# ECG.net
KiCad netlist of a schematic drawn in EAGLE
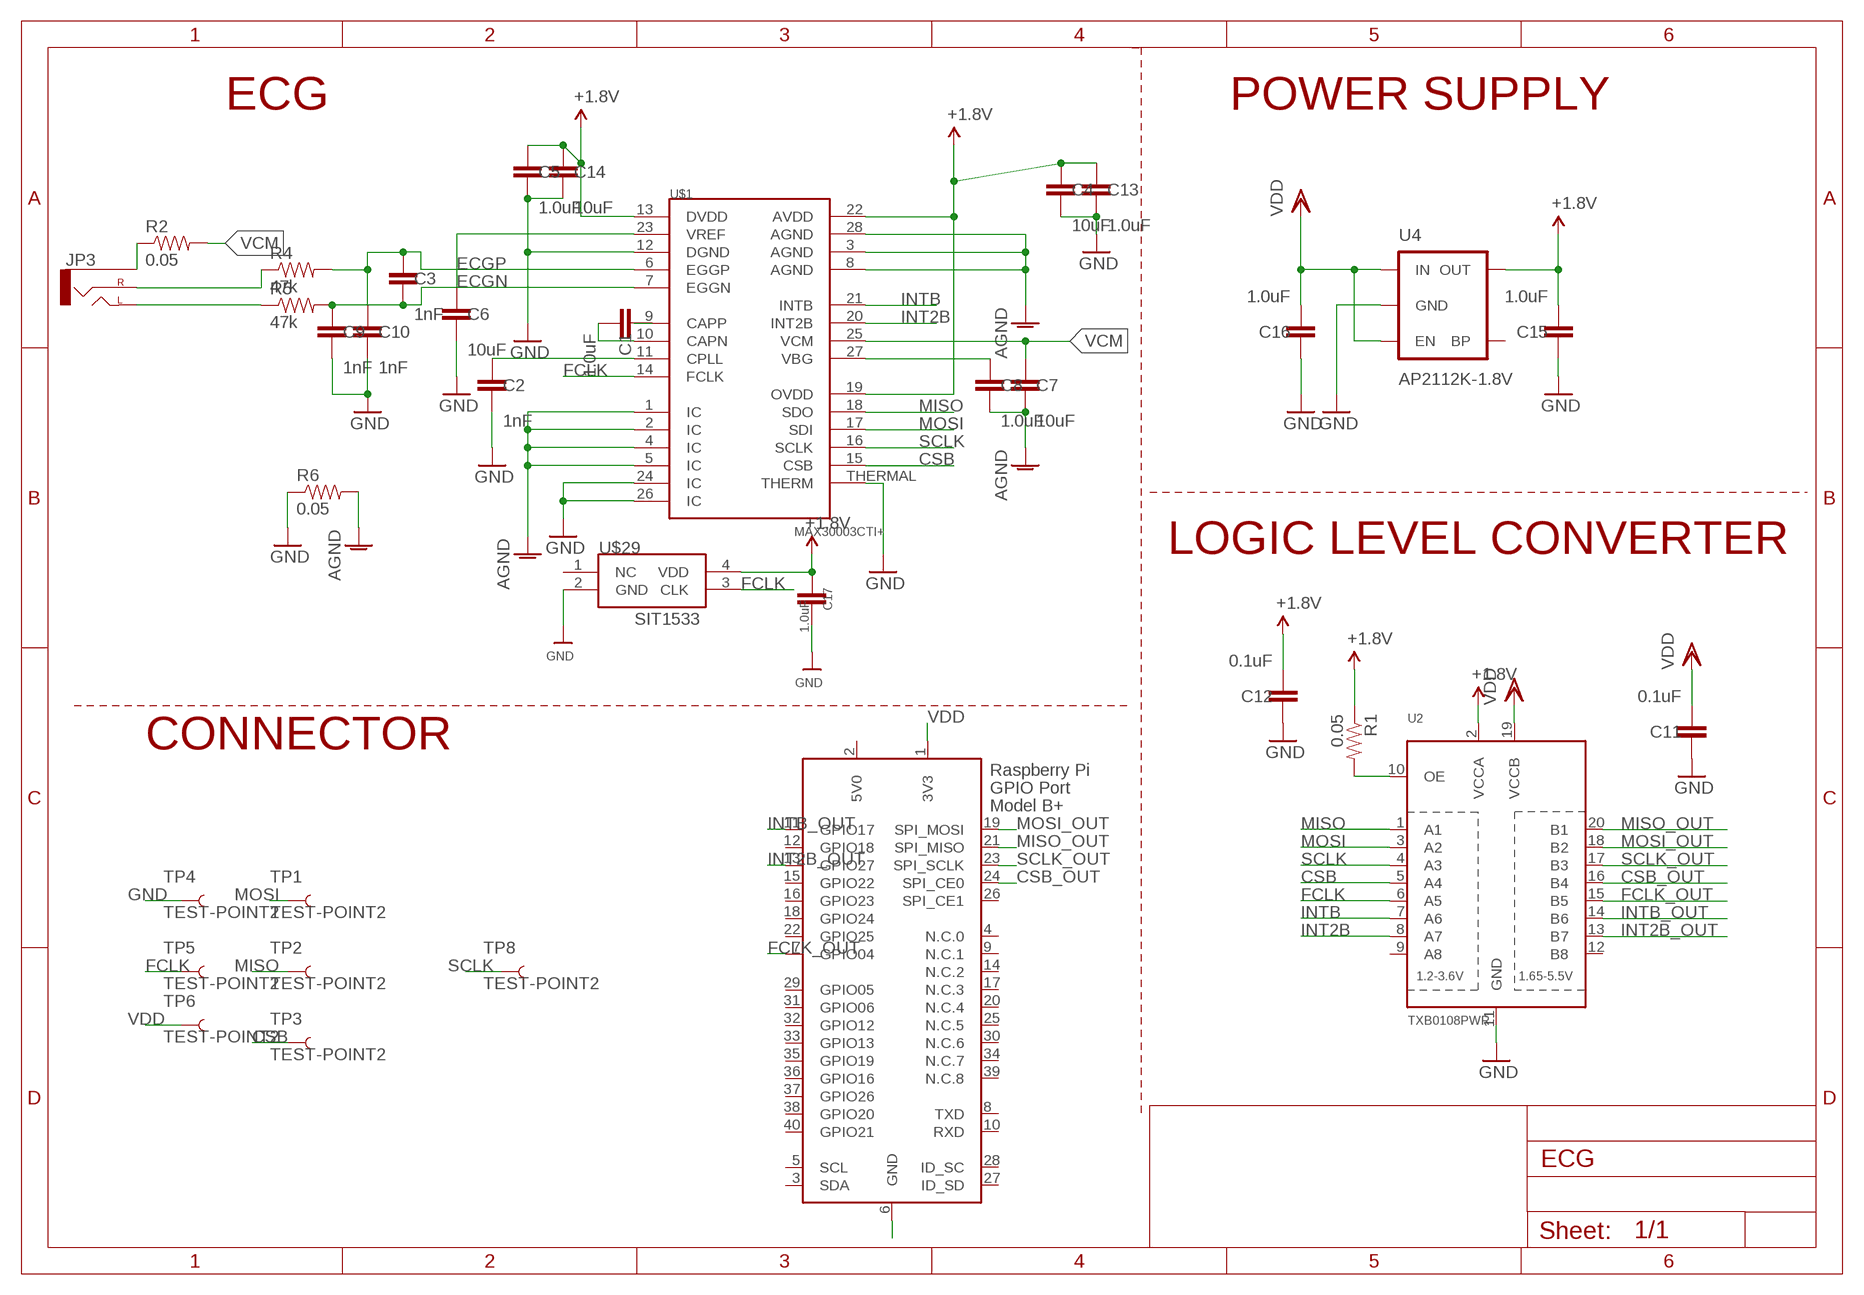
[diagram p0: schematic, sheet 1]

(export (version "E")
  (design (tool "Eeschema 10.0.6"))
  (components
    (comp (ref "C1")
      (value "1.0uF")
      (footprint "eagle-import:0603")
      (libsource (lib "eagle-import") (part "1.0UF-0603-16V-10%"))
    )
    (comp (ref "C2")
      (value "1nF")
      (footprint "eagle-import:0603")
      (libsource (lib "eagle-import") (part "1.0NF/1000PF-0603-50V-10%"))
    )
    (comp (ref "C3")
      (value "1nF")
      (footprint "eagle-import:0603")
      (libsource (lib "eagle-import") (part "1.0NF/1000PF-0603-50V-10%"))
    )
    (comp (ref "C4")
      (value "10uF")
      (footprint "eagle-import:0603")
      (libsource (lib "eagle-import") (part "10UF-0603-6.3V-20%"))
    )
    (comp (ref "C5")
      (value "1.0uF")
      (footprint "eagle-import:0603")
      (libsource (lib "eagle-import") (part "1.0UF-0603-16V-10%"))
    )
    (comp (ref "C6")
      (value "10uF")
      (footprint "eagle-import:0603")
      (libsource (lib "eagle-import") (part "10UF-0603-6.3V-20%"))
    )
    (comp (ref "C7")
      (value "10uF")
      (footprint "eagle-import:0603")
      (libsource (lib "eagle-import") (part "10UF-0603-6.3V-20%"))
    )
    (comp (ref "C8")
      (value "1.0uF")
      (footprint "eagle-import:0603")
      (libsource (lib "eagle-import") (part "1.0UF-0603-16V-10%"))
    )
    (comp (ref "C9")
      (value "1nF")
      (footprint "eagle-import:0603")
      (libsource (lib "eagle-import") (part "1.0NF/1000PF-0603-50V-10%"))
    )
    (comp (ref "C10")
      (value "1nF")
      (footprint "eagle-import:0603")
      (libsource (lib "eagle-import") (part "1.0NF/1000PF-0603-50V-10%"))
    )
    (comp (ref "C11")
      (value "0.1uF")
      (footprint "eagle-import:0603")
      (libsource (lib "eagle-import") (part "0.1UF-0603-25V-(+80/-20%)"))
    )
    (comp (ref "C12")
      (value "0.1uF")
      (footprint "eagle-import:0603")
      (libsource (lib "eagle-import") (part "0.1UF-0603-25V-(+80/-20%)"))
    )
    (comp (ref "C13")
      (value "1.0uF")
      (footprint "eagle-import:0603")
      (libsource (lib "eagle-import") (part "1.0UF-0603-16V-10%"))
    )
    (comp (ref "C14")
      (value "10uF")
      (footprint "eagle-import:0603")
      (libsource (lib "eagle-import") (part "10UF-0603-6.3V-20%"))
    )
    (comp (ref "C15")
      (value "1.0uF")
      (footprint "eagle-import:0603")
      (libsource (lib "eagle-import") (part "1.0UF-0603-16V-10%"))
    )
    (comp (ref "C16")
      (value "1.0uF")
      (footprint "eagle-import:0603")
      (libsource (lib "eagle-import") (part "1.0UF-0603-16V-10%"))
    )
    (comp (ref "C17")
      (value "1.0uF")
      (footprint "eagle-import:0603")
      (libsource (lib "eagle-import") (part "1.0UF-0603-16V-10%"))
    )
    (comp (ref "JP3")
      (value "AUDIO-JACKSMD2")
      (footprint "eagle-import:AUDIO-JACK-3.5MM-SMD")
      (libsource (lib "eagle-import") (part "AUDIO-JACKSMD2"))
    )
    (comp (ref "R1")
      (value "0.05")
      (footprint "eagle-import:0603")
      (libsource (lib "eagle-import") (part "0.05OHM-0603-1/5W-1%"))
    )
    (comp (ref "R2")
      (value "0.05")
      (footprint "eagle-import:0603")
      (libsource (lib "eagle-import") (part "0.05OHM-0603-1/5W-1%"))
    )
    (comp (ref "R4")
      (value "47k")
      (footprint "eagle-import:0603")
      (libsource (lib "eagle-import") (part "47KOHM-0603-1/10W-1%"))
    )
    (comp (ref "R5")
      (value "47k")
      (footprint "eagle-import:0603")
      (libsource (lib "eagle-import") (part "47KOHM-0603-1/10W-1%"))
    )
    (comp (ref "R6")
      (value "0.05")
      (footprint "eagle-import:0603")
      (libsource (lib "eagle-import") (part "0.05OHM-0603-1/5W-1%"))
    )
    (comp (ref "TP1")
      (value "TEST-POINT2")
      (footprint "eagle-import:PAD.02X.02")
      (libsource (lib "eagle-import") (part "TEST-POINT2"))
    )
    (comp (ref "TP2")
      (value "TEST-POINT2")
      (footprint "eagle-import:PAD.02X.02")
      (libsource (lib "eagle-import") (part "TEST-POINT2"))
    )
    (comp (ref "TP3")
      (value "TEST-POINT2")
      (footprint "eagle-import:PAD.02X.02")
      (libsource (lib "eagle-import") (part "TEST-POINT2"))
    )
    (comp (ref "TP4")
      (value "TEST-POINT2")
      (footprint "eagle-import:PAD.02X.02")
      (libsource (lib "eagle-import") (part "TEST-POINT2"))
    )
    (comp (ref "TP5")
      (value "TEST-POINT2")
      (footprint "eagle-import:PAD.02X.02")
      (libsource (lib "eagle-import") (part "TEST-POINT2"))
    )
    (comp (ref "TP6")
      (value "TEST-POINT2")
      (footprint "eagle-import:PAD.02X.02")
      (libsource (lib "eagle-import") (part "TEST-POINT2"))
    )
    (comp (ref "TP8")
      (value "TEST-POINT2")
      (footprint "eagle-import:PAD.02X.02")
      (libsource (lib "eagle-import") (part "TEST-POINT2"))
    )
    (comp (ref "U$1")
      (value "MAX30003CTI+")
      (footprint "eagle-import:QFN-28")
      (libsource (lib "eagle-import") (part "MAX30003"))
    )
    (comp (ref "U$29")
      (value "SIT1533")
      (footprint "eagle-import:SIT1533")
      (libsource (lib "eagle-import") (part "SIT1533"))
    )
    (comp (ref "U2")
      (value "TXB0108PWR")
      (footprint "eagle-import:TSSOP20")
      (libsource (lib "eagle-import") (part "TXB0108PWR"))
    )
    (comp (ref "U4")
      (value "AP2112K-1.8V")
      (footprint "eagle-import:SOT23-5")
      (libsource (lib "eagle-import") (part "V_REG_LDOSMD"))
    )
    (comp (ref "X1")
      (value "RASPI_BOARD_B+_HDC")
      (footprint "eagle-import:RASPI_BOARD_B+HAT_DF_CF")
      (libsource (lib "eagle-import") (part "RASPI_BOARD_B+_HDC"))
    )
  )
  (nets
    (net (code "1") (name "+1.8V") (class "Default")
      (node (ref "C12") (pin "2") (pinfunction "2_2") (pintype "passive"))
      (node (ref "C13") (pin "1") (pinfunction "1_1") (pintype "passive"))
      (node (ref "C14") (pin "1") (pinfunction "1_1") (pintype "passive"))
      (node (ref "C15") (pin "2") (pinfunction "2_2") (pintype "passive"))
      (node (ref "C17") (pin "1") (pinfunction "1_1") (pintype "passive"))
      (node (ref "C4") (pin "1") (pinfunction "1_1") (pintype "passive"))
      (node (ref "C5") (pin "1") (pinfunction "1_1") (pintype "passive"))
      (node (ref "R1") (pin "1") (pinfunction "1_1") (pintype "passive"))
      (node (ref "U$1") (pin "13") (pinfunction "DVDD_13") (pintype "bidirectional"))
      (node (ref "U$1") (pin "19") (pinfunction "OVDD_19") (pintype "bidirectional"))
      (node (ref "U$1") (pin "22") (pinfunction "AVDD_22") (pintype "bidirectional"))
      (node (ref "U$29") (pin "4") (pinfunction "VDD_4") (pintype "bidirectional"))
      (node (ref "U2") (pin "2") (pinfunction "VCCA_2") (pintype "bidirectional"))
      (node (ref "U4") (pin "5") (pinfunction "OUT_5") (pintype "passive"))
    )
    (net (code "2") (name "/5V0") (class "Default")
      (node (ref "X1") (pin "2") (pinfunction "5V0_2") (pintype "power_in"))
    )
    (net (code "3") (name "/CSB") (class "Default")
      (node (ref "TP3") (pin "P$1") (pinfunction "1_P$1") (pintype "bidirectional"))
      (node (ref "U$1") (pin "15") (pinfunction "CSB_15") (pintype "bidirectional"))
      (node (ref "U2") (pin "5") (pinfunction "A4_5") (pintype "bidirectional"))
    )
    (net (code "4") (name "/CSB_OUT") (class "Default")
      (node (ref "U2") (pin "16") (pinfunction "B4_16") (pintype "bidirectional"))
      (node (ref "X1") (pin "24") (pinfunction "SPI_CE0_24") (pintype "bidirectional"))
    )
    (net (code "5") (name "/ECGN") (class "Default")
      (node (ref "C3") (pin "2") (pinfunction "2_2") (pintype "passive"))
      (node (ref "C9") (pin "1") (pinfunction "1_1") (pintype "passive"))
      (node (ref "R5") (pin "2") (pinfunction "2_2") (pintype "passive"))
      (node (ref "U$1") (pin "7") (pinfunction "EGGN_7") (pintype "bidirectional"))
    )
    (net (code "6") (name "/ECGP") (class "Default")
      (node (ref "C10") (pin "1") (pinfunction "1_1") (pintype "passive"))
      (node (ref "C3") (pin "1") (pinfunction "1_1") (pintype "passive"))
      (node (ref "R4") (pin "2") (pinfunction "2_2") (pintype "passive"))
      (node (ref "U$1") (pin "6") (pinfunction "EGGP_6") (pintype "bidirectional"))
    )
    (net (code "7") (name "/FCLK") (class "Default")
      (node (ref "TP5") (pin "P$1") (pinfunction "1_P$1") (pintype "bidirectional"))
      (node (ref "U$1") (pin "14") (pinfunction "FCLK_14") (pintype "bidirectional"))
      (node (ref "U$29") (pin "3") (pinfunction "CLK_3") (pintype "bidirectional"))
      (node (ref "U2") (pin "6") (pinfunction "A5_6") (pintype "bidirectional"))
    )
    (net (code "8") (name "/FCLK_OUT") (class "Default")
      (node (ref "U2") (pin "15") (pinfunction "B5_15") (pintype "bidirectional"))
      (node (ref "X1") (pin "7") (pinfunction "GPIO04_7") (pintype "bidirectional"))
    )
    (net (code "9") (name "/INT2B") (class "Default")
      (node (ref "U$1") (pin "20") (pinfunction "INT2B_20") (pintype "bidirectional"))
      (node (ref "U2") (pin "8") (pinfunction "A7_8") (pintype "bidirectional"))
    )
    (net (code "10") (name "/INT2B_OUT") (class "Default")
      (node (ref "U2") (pin "13") (pinfunction "B7_13") (pintype "bidirectional"))
      (node (ref "X1") (pin "13") (pinfunction "GPIO27_13") (pintype "bidirectional"))
    )
    (net (code "11") (name "/INTB") (class "Default")
      (node (ref "U$1") (pin "21") (pinfunction "INTB_21") (pintype "bidirectional"))
      (node (ref "U2") (pin "7") (pinfunction "A6_7") (pintype "bidirectional"))
    )
    (net (code "12") (name "/INTB_OUT") (class "Default")
      (node (ref "U2") (pin "14") (pinfunction "B6_14") (pintype "bidirectional"))
      (node (ref "X1") (pin "11") (pinfunction "GPIO17_11") (pintype "bidirectional"))
    )
    (net (code "13") (name "/MISO") (class "Default")
      (node (ref "TP2") (pin "P$1") (pinfunction "1_P$1") (pintype "bidirectional"))
      (node (ref "U$1") (pin "18") (pinfunction "SDO_18") (pintype "bidirectional"))
      (node (ref "U2") (pin "1") (pinfunction "A1_1") (pintype "bidirectional"))
    )
    (net (code "14") (name "/MISO_OUT") (class "Default")
      (node (ref "U2") (pin "20") (pinfunction "B1_20") (pintype "bidirectional"))
      (node (ref "X1") (pin "21") (pinfunction "SPI_MISO_21") (pintype "bidirectional"))
    )
    (net (code "15") (name "/MOSI") (class "Default")
      (node (ref "TP1") (pin "P$1") (pinfunction "1_P$1") (pintype "bidirectional"))
      (node (ref "U$1") (pin "17") (pinfunction "SDI_17") (pintype "bidirectional"))
      (node (ref "U2") (pin "3") (pinfunction "A2_3") (pintype "bidirectional"))
    )
    (net (code "16") (name "/MOSI_OUT") (class "Default")
      (node (ref "U2") (pin "18") (pinfunction "B2_18") (pintype "bidirectional"))
      (node (ref "X1") (pin "19") (pinfunction "SPI_MOSI_19") (pintype "bidirectional"))
    )
    (net (code "17") (name "/SCLK") (class "Default")
      (node (ref "TP8") (pin "P$1") (pinfunction "1_P$1") (pintype "bidirectional"))
      (node (ref "U$1") (pin "16") (pinfunction "SCLK_16") (pintype "bidirectional"))
      (node (ref "U2") (pin "4") (pinfunction "A3_4") (pintype "bidirectional"))
    )
    (net (code "18") (name "/SCLK_OUT") (class "Default")
      (node (ref "U2") (pin "17") (pinfunction "B3_17") (pintype "bidirectional"))
      (node (ref "X1") (pin "23") (pinfunction "SPI_SCLK_23") (pintype "bidirectional"))
    )
    (net (code "19") (name "AGND") (class "Default")
      (node (ref "C7") (pin "2") (pinfunction "2_2") (pintype "passive"))
      (node (ref "C8") (pin "2") (pinfunction "2_2") (pintype "passive"))
      (node (ref "R6") (pin "2") (pinfunction "2_2") (pintype "passive"))
      (node (ref "U$1") (pin "1") (pinfunction "IC_1") (pintype "bidirectional"))
      (node (ref "U$1") (pin "2") (pinfunction "IC_2") (pintype "bidirectional"))
      (node (ref "U$1") (pin "28") (pinfunction "AGND_28") (pintype "bidirectional"))
      (node (ref "U$1") (pin "3") (pinfunction "AGND_3") (pintype "bidirectional"))
      (node (ref "U$1") (pin "4") (pinfunction "IC_4") (pintype "bidirectional"))
      (node (ref "U$1") (pin "5") (pinfunction "IC_5") (pintype "bidirectional"))
      (node (ref "U$1") (pin "8") (pinfunction "AGND_8") (pintype "bidirectional"))
    )
    (net (code "20") (name "GND") (class "Default")
      (node (ref "C10") (pin "2") (pinfunction "2_2") (pintype "passive"))
      (node (ref "C11") (pin "1") (pinfunction "1_1") (pintype "passive"))
      (node (ref "C12") (pin "1") (pinfunction "1_1") (pintype "passive"))
      (node (ref "C13") (pin "2") (pinfunction "2_2") (pintype "passive"))
      (node (ref "C14") (pin "2") (pinfunction "2_2") (pintype "passive"))
      (node (ref "C15") (pin "1") (pinfunction "1_1") (pintype "passive"))
      (node (ref "C16") (pin "1") (pinfunction "1_1") (pintype "passive"))
      (node (ref "C17") (pin "2") (pinfunction "2_2") (pintype "passive"))
      (node (ref "C2") (pin "2") (pinfunction "2_2") (pintype "passive"))
      (node (ref "C4") (pin "2") (pinfunction "2_2") (pintype "passive"))
      (node (ref "C5") (pin "2") (pinfunction "2_2") (pintype "passive"))
      (node (ref "C6") (pin "2") (pinfunction "2_2") (pintype "passive"))
      (node (ref "C9") (pin "2") (pinfunction "2_2") (pintype "passive"))
      (node (ref "R6") (pin "1") (pinfunction "1_1") (pintype "passive"))
      (node (ref "TP4") (pin "P$1") (pinfunction "1_P$1") (pintype "bidirectional"))
      (node (ref "U$1") (pin "12") (pinfunction "DGND_12") (pintype "bidirectional"))
      (node (ref "U$1") (pin "24") (pinfunction "IC_24") (pintype "bidirectional"))
      (node (ref "U$1") (pin "26") (pinfunction "IC_26") (pintype "bidirectional"))
      (node (ref "U$1") (pin "THERMAL") (pinfunction "THERM_THERMAL") (pintype "bidirectional"))
      (node (ref "U$29") (pin "2") (pinfunction "GND_2") (pintype "bidirectional"))
      (node (ref "U2") (pin "11") (pinfunction "GND_11") (pintype "bidirectional"))
      (node (ref "U4") (pin "2") (pinfunction "GND_2") (pintype "input"))
    )
    (net (code "21") (name "Net-(JP3-LEFT)") (class "Default")
      (node (ref "JP3") (pin "TIP") (pinfunction "LEFT_TIP") (pintype "bidirectional"))
      (node (ref "R5") (pin "1") (pinfunction "1_1") (pintype "passive"))
    )
    (net (code "22") (name "Net-(JP3-PadSLEEVE)") (class "Default")
      (node (ref "JP3") (pin "SLEEVE") (pinfunction "SLEEVE_SLEEVE") (pintype "bidirectional"))
      (node (ref "R2") (pin "1") (pinfunction "1_1") (pintype "passive"))
    )
    (net (code "23") (name "Net-(JP3-RIGHT)") (class "Default")
      (node (ref "JP3") (pin "RING") (pinfunction "RIGHT_RING") (pintype "bidirectional"))
      (node (ref "R4") (pin "1") (pinfunction "1_1") (pintype "passive"))
    )
    (net (code "24") (name "Net-(U$1-CAPN)") (class "Default")
      (node (ref "C1") (pin "2") (pinfunction "2_2") (pintype "passive"))
      (node (ref "U$1") (pin "10") (pinfunction "CAPN_10") (pintype "bidirectional"))
    )
    (net (code "25") (name "Net-(U$1-CAPP)") (class "Default")
      (node (ref "C1") (pin "1") (pinfunction "1_1") (pintype "passive"))
      (node (ref "U$1") (pin "9") (pinfunction "CAPP_9") (pintype "bidirectional"))
    )
    (net (code "26") (name "Net-(U$1-CPLL)") (class "Default")
      (node (ref "C2") (pin "1") (pinfunction "1_1") (pintype "passive"))
      (node (ref "U$1") (pin "11") (pinfunction "CPLL_11") (pintype "bidirectional"))
    )
    (net (code "27") (name "Net-(U$1-VBG)") (class "Default")
      (node (ref "C8") (pin "1") (pinfunction "1_1") (pintype "passive"))
      (node (ref "U$1") (pin "27") (pinfunction "VBG_27") (pintype "bidirectional"))
    )
    (net (code "28") (name "Net-(U$1-VREF)") (class "Default")
      (node (ref "C6") (pin "1") (pinfunction "1_1") (pintype "passive"))
      (node (ref "U$1") (pin "23") (pinfunction "VREF_23") (pintype "bidirectional"))
    )
    (net (code "29") (name "Net-(U2-OE)") (class "Default")
      (node (ref "R1") (pin "2") (pinfunction "2_2") (pintype "passive"))
      (node (ref "U2") (pin "10") (pinfunction "OE_10") (pintype "bidirectional"))
    )
    (net (code "30") (name "VCM") (class "Default")
      (node (ref "C7") (pin "1") (pinfunction "1_1") (pintype "passive"))
      (node (ref "R2") (pin "2") (pinfunction "2_2") (pintype "passive"))
      (node (ref "U$1") (pin "25") (pinfunction "VCM_25") (pintype "bidirectional"))
    )
    (net (code "31") (name "VDD") (class "Default")
      (node (ref "C11") (pin "2") (pinfunction "2_2") (pintype "passive"))
      (node (ref "C16") (pin "2") (pinfunction "2_2") (pintype "passive"))
      (node (ref "TP6") (pin "P$1") (pinfunction "1_P$1") (pintype "bidirectional"))
      (node (ref "U2") (pin "19") (pinfunction "VCCB_19") (pintype "bidirectional"))
      (node (ref "U4") (pin "1") (pinfunction "IN_1") (pintype "input"))
      (node (ref "U4") (pin "3") (pinfunction "EN_3") (pintype "input"))
      (node (ref "X1") (pin "1") (pinfunction "3V3_1") (pintype "power_in"))
    )
    (net (code "32") (name "unconnected-(U$29-NC-Pad1)") (class "Default")
      (node (ref "U$29") (pin "1") (pinfunction "NC_1") (pintype "bidirectional"))
    )
    (net (code "33") (name "unconnected-(U2-A8-Pad9)") (class "Default")
      (node (ref "U2") (pin "9") (pinfunction "A8_9") (pintype "bidirectional"))
    )
    (net (code "34") (name "unconnected-(U2-B8-Pad12)") (class "Default")
      (node (ref "U2") (pin "12") (pinfunction "B8_12") (pintype "bidirectional"))
    )
    (net (code "35") (name "unconnected-(U4-BP-Pad4)") (class "Default")
      (node (ref "U4") (pin "4") (pinfunction "BP_4") (pintype "input"))
    )
    (net (code "36") (name "unconnected-(X1-GND-Pad6)") (class "Default")
      (node (ref "X1") (pin "6") (pinfunction "GND_6") (pintype "power_in"))
    )
    (net (code "37") (name "unconnected-(X1-GPIO05-Pad29)") (class "Default")
      (node (ref "X1") (pin "29") (pinfunction "GPIO05_29") (pintype "no_connect"))
    )
    (net (code "38") (name "unconnected-(X1-GPIO06-Pad31)") (class "Default")
      (node (ref "X1") (pin "31") (pinfunction "GPIO06_31") (pintype "no_connect"))
    )
    (net (code "39") (name "unconnected-(X1-GPIO12-Pad32)") (class "Default")
      (node (ref "X1") (pin "32") (pinfunction "GPIO12_32") (pintype "no_connect"))
    )
    (net (code "40") (name "unconnected-(X1-GPIO13-Pad33)") (class "Default")
      (node (ref "X1") (pin "33") (pinfunction "GPIO13_33") (pintype "no_connect"))
    )
    (net (code "41") (name "unconnected-(X1-GPIO16-Pad36)") (class "Default")
      (node (ref "X1") (pin "36") (pinfunction "GPIO16_36") (pintype "no_connect"))
    )
    (net (code "42") (name "unconnected-(X1-GPIO18-Pad12)") (class "Default")
      (node (ref "X1") (pin "12") (pinfunction "GPIO18_12") (pintype "bidirectional"))
    )
    (net (code "43") (name "unconnected-(X1-GPIO19-Pad35)") (class "Default")
      (node (ref "X1") (pin "35") (pinfunction "GPIO19_35") (pintype "no_connect"))
    )
    (net (code "44") (name "unconnected-(X1-GPIO20-Pad38)") (class "Default")
      (node (ref "X1") (pin "38") (pinfunction "GPIO20_38") (pintype "no_connect"))
    )
    (net (code "45") (name "unconnected-(X1-GPIO21-Pad40)") (class "Default")
      (node (ref "X1") (pin "40") (pinfunction "GPIO21_40") (pintype "no_connect"))
    )
    (net (code "46") (name "unconnected-(X1-GPIO22-Pad15)") (class "Default")
      (node (ref "X1") (pin "15") (pinfunction "GPIO22_15") (pintype "bidirectional"))
    )
    (net (code "47") (name "unconnected-(X1-GPIO23-Pad16)") (class "Default")
      (node (ref "X1") (pin "16") (pinfunction "GPIO23_16") (pintype "bidirectional"))
    )
    (net (code "48") (name "unconnected-(X1-GPIO24-Pad18)") (class "Default")
      (node (ref "X1") (pin "18") (pinfunction "GPIO24_18") (pintype "bidirectional"))
    )
    (net (code "49") (name "unconnected-(X1-GPIO25-Pad22)") (class "Default")
      (node (ref "X1") (pin "22") (pinfunction "GPIO25_22") (pintype "bidirectional"))
    )
    (net (code "50") (name "unconnected-(X1-GPIO26-Pad37)") (class "Default")
      (node (ref "X1") (pin "37") (pinfunction "GPIO26_37") (pintype "no_connect"))
    )
    (net (code "51") (name "unconnected-(X1-ID_SC-Pad28)") (class "Default")
      (node (ref "X1") (pin "28") (pinfunction "ID_SC_28") (pintype "no_connect"))
    )
    (net (code "52") (name "unconnected-(X1-ID_SD-Pad27)") (class "Default")
      (node (ref "X1") (pin "27") (pinfunction "ID_SD_27") (pintype "no_connect"))
    )
    (net (code "53") (name "unconnected-(X1-N.C.0-Pad4)") (class "Default")
      (node (ref "X1") (pin "4") (pinfunction "N.C.0_4") (pintype "no_connect"))
    )
    (net (code "54") (name "unconnected-(X1-N.C.1-Pad9)") (class "Default")
      (node (ref "X1") (pin "9") (pinfunction "N.C.1_9") (pintype "no_connect"))
    )
    (net (code "55") (name "unconnected-(X1-N.C.2-Pad14)") (class "Default")
      (node (ref "X1") (pin "14") (pinfunction "N.C.2_14") (pintype "no_connect"))
    )
    (net (code "56") (name "unconnected-(X1-N.C.3-Pad17)") (class "Default")
      (node (ref "X1") (pin "17") (pinfunction "N.C.3_17") (pintype "no_connect"))
    )
    (net (code "57") (name "unconnected-(X1-N.C.4-Pad20)") (class "Default")
      (node (ref "X1") (pin "20") (pinfunction "N.C.4_20") (pintype "no_connect"))
    )
    (net (code "58") (name "unconnected-(X1-N.C.5-Pad25)") (class "Default")
      (node (ref "X1") (pin "25") (pinfunction "N.C.5_25") (pintype "no_connect"))
    )
    (net (code "59") (name "unconnected-(X1-N.C.6-Pad30)") (class "Default")
      (node (ref "X1") (pin "30") (pinfunction "N.C.6_30") (pintype "no_connect"))
    )
    (net (code "60") (name "unconnected-(X1-N.C.7-Pad34)") (class "Default")
      (node (ref "X1") (pin "34") (pinfunction "N.C.7_34") (pintype "no_connect"))
    )
    (net (code "61") (name "unconnected-(X1-N.C.8-Pad39)") (class "Default")
      (node (ref "X1") (pin "39") (pinfunction "N.C.8_39") (pintype "no_connect"))
    )
    (net (code "62") (name "unconnected-(X1-RXD-Pad10)") (class "Default")
      (node (ref "X1") (pin "10") (pinfunction "RXD_10") (pintype "bidirectional"))
    )
    (net (code "63") (name "unconnected-(X1-SCL-Pad5)") (class "Default")
      (node (ref "X1") (pin "5") (pinfunction "SCL_5") (pintype "bidirectional"))
    )
    (net (code "64") (name "unconnected-(X1-SDA-Pad3)") (class "Default")
      (node (ref "X1") (pin "3") (pinfunction "SDA_3") (pintype "bidirectional"))
    )
    (net (code "65") (name "unconnected-(X1-SPI_CE1-Pad26)") (class "Default")
      (node (ref "X1") (pin "26") (pinfunction "SPI_CE1_26") (pintype "bidirectional"))
    )
    (net (code "66") (name "unconnected-(X1-TXD-Pad8)") (class "Default")
      (node (ref "X1") (pin "8") (pinfunction "TXD_8") (pintype "bidirectional"))
    )
  )
)
